# RpiServoStepper_v3.net
KiCad netlist of a schematic drawn in EAGLE
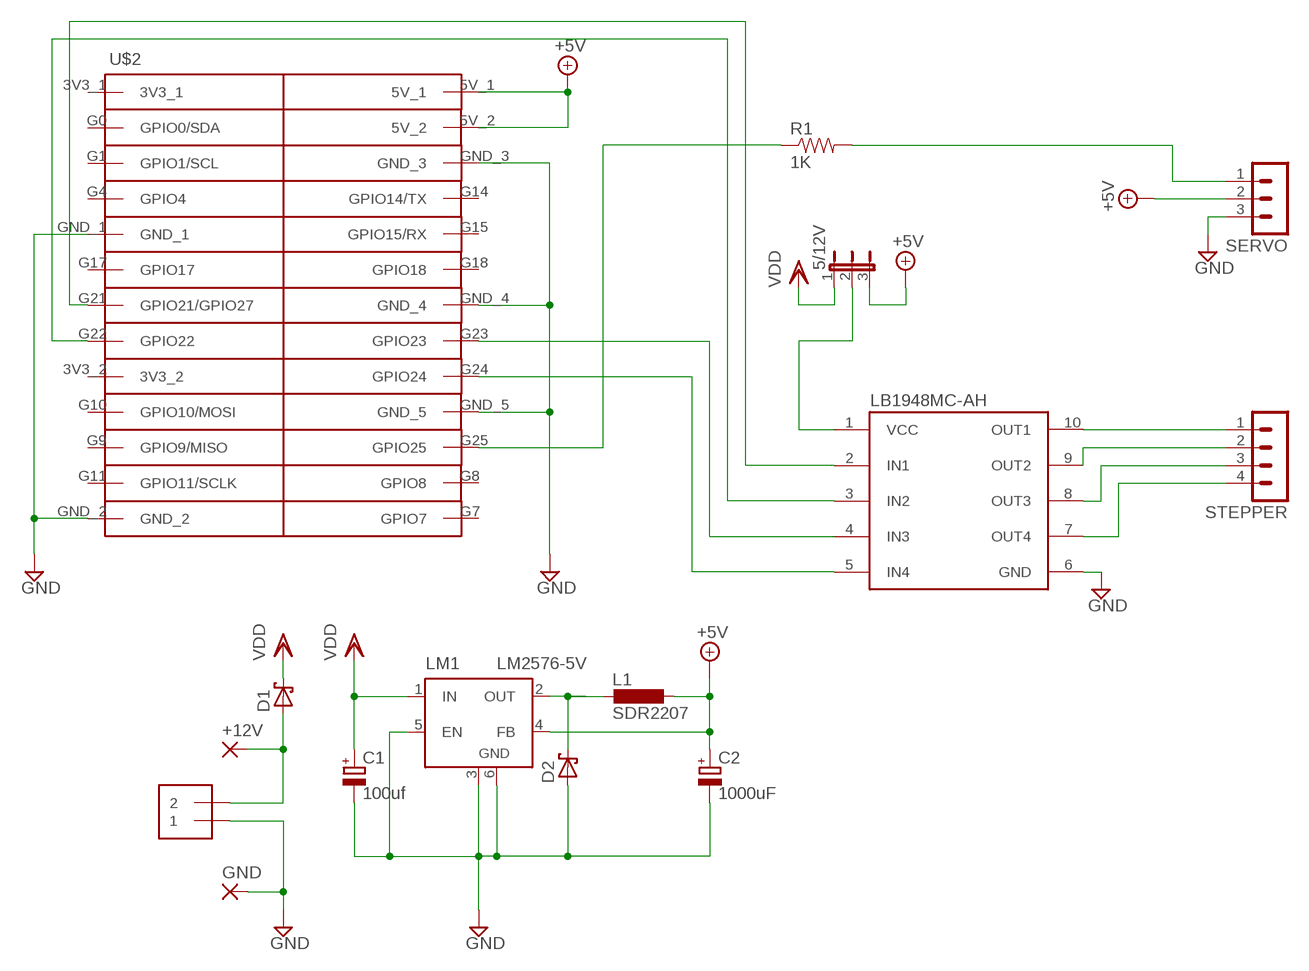
[diagram p0: schematic, sheet 1]

(export (version "E")
  (design (tool "Eeschema 10.0.6"))
  (components
    (comp (ref "+12V")
      (value "3,81/1,4")
      (footprint "eagle-import:3,81_1,4")
      (libsource (lib "eagle-import") (part "3,81/1,4"))
    )
    (comp (ref "5/12V")
      (value "JP2E")
      (footprint "eagle-import:JP2")
      (libsource (lib "eagle-import") (part "JP2E"))
    )
    (comp (ref "C1")
      (value "100uf")
      (footprint "eagle-import:PANASONIC_E")
      (libsource (lib "eagle-import") (part "CPOL-EUE"))
    )
    (comp (ref "C2")
      (value "1000uF")
      (footprint "eagle-import:PANASONIC_G")
      (libsource (lib "eagle-import") (part "CPOL-EUG"))
    )
    (comp (ref "D1")
      (value "SCHOTTKY-DIODESMC")
      (footprint "eagle-import:SMC")
      (libsource (lib "eagle-import") (part "SCHOTTKY-DIODESMC"))
    )
    (comp (ref "D2")
      (value "SCHOTTKY-DIODESMC")
      (footprint "eagle-import:SMC")
      (libsource (lib "eagle-import") (part "SCHOTTKY-DIODESMC"))
    )
    (comp (ref "GND")
      (value "3,81/1,4")
      (footprint "eagle-import:3,81_1,4")
      (libsource (lib "eagle-import") (part "3,81/1,4"))
    )
    (comp (ref "J1")
      (value "1X2-3.5MM")
      (footprint "eagle-import:3.5MMTERM")
      (libsource (lib "eagle-import") (part "1X2-3.5MM"))
    )
    (comp (ref "L1")
      (value "SDR2207")
      (footprint "eagle-import:SM")
      (libsource (lib "eagle-import") (part "SDR2207"))
    )
    (comp (ref "LB1948MC-AH")
      (value "LB1948MC-AH")
      (footprint "eagle-import:SOIC-10")
      (libsource (lib "eagle-import") (part "LB1948MC-AH"))
    )
    (comp (ref "LM1")
      (value "LM2576-5V")
      (footprint "eagle-import:TO263-5")
      (libsource (lib "eagle-import") (part "LM2596S"))
    )
    (comp (ref "R1")
      (value "1K")
      (footprint "eagle-import:1206")
      (libsource (lib "eagle-import") (part "RESISTOR1206"))
    )
    (comp (ref "SERVO")
      (value "MA03-1")
      (footprint "eagle-import:MA03-1")
      (libsource (lib "eagle-import") (part "MA03-1"))
    )
    (comp (ref "STEPPER")
      (value "MA04-1")
      (footprint "eagle-import:MA04-1")
      (libsource (lib "eagle-import") (part "MA04-1"))
    )
    (comp (ref "U$2")
      (value "CONNECTEUR_RPI")
      (footprint "eagle-import:26PIN")
      (libsource (lib "eagle-import") (part "CONNECTEUR_RPI"))
    )
  )
  (nets
    (net (code "1") (name "+5V") (class "Default")
      (node (ref "5/12V") (pin "3") (pinfunction "3_3") (pintype "passive"))
      (node (ref "C2") (pin "+") (pinfunction "+_+") (pintype "passive"))
      (node (ref "L1") (pin "P$2") (pinfunction "2_P$2") (pintype "passive"))
      (node (ref "LM1") (pin "4") (pinfunction "FB_4") (pintype "input"))
      (node (ref "SERVO") (pin "2") (pinfunction "2_2") (pintype "passive"))
      (node (ref "U$2") (pin "5V_1") (pinfunction "5V_1_5V_1") (pintype "bidirectional"))
      (node (ref "U$2") (pin "5V_2") (pinfunction "5V_2_5V_2") (pintype "bidirectional"))
    )
    (net (code "2") (name "GND") (class "Default")
      (node (ref "C1") (pin "-") (pinfunction "-_-") (pintype "passive"))
      (node (ref "C2") (pin "-") (pinfunction "-_-") (pintype "passive"))
      (node (ref "D2") (pin "A") (pinfunction "A_A") (pintype "passive"))
      (node (ref "GND") (pin "1") (pinfunction "P_1") (pintype "passive"))
      (node (ref "J1") (pin "1") (pinfunction "1_1") (pintype "passive"))
      (node (ref "LB1948MC-AH") (pin "6") (pinfunction "GND_6") (pintype "bidirectional"))
      (node (ref "LM1") (pin "3") (pinfunction "GND_3") (pintype "power_in"))
      (node (ref "LM1") (pin "5") (pinfunction "EN_5") (pintype "input"))
      (node (ref "LM1") (pin "6") (pinfunction "GND_6") (pintype "power_in"))
      (node (ref "SERVO") (pin "3") (pinfunction "3_3") (pintype "passive"))
      (node (ref "U$2") (pin "GND_1") (pinfunction "GND_1_GND_1") (pintype "bidirectional"))
      (node (ref "U$2") (pin "GND_2") (pinfunction "GND_2_GND_2") (pintype "bidirectional"))
      (node (ref "U$2") (pin "GND_3") (pinfunction "GND_3_GND_3") (pintype "bidirectional"))
      (node (ref "U$2") (pin "GND_4") (pinfunction "GND_4_GND_4") (pintype "bidirectional"))
      (node (ref "U$2") (pin "GND_5") (pinfunction "GND_5_GND_5") (pintype "bidirectional"))
    )
    (net (code "3") (name "Net-(+12V-P)") (class "Default")
      (node (ref "+12V") (pin "1") (pinfunction "P_1") (pintype "passive"))
      (node (ref "D1") (pin "A") (pinfunction "A_A") (pintype "passive"))
      (node (ref "J1") (pin "2") (pinfunction "2_2") (pintype "passive"))
    )
    (net (code "4") (name "Net-(L1-1)") (class "Default")
      (node (ref "D2") (pin "C") (pinfunction "C_C") (pintype "passive"))
      (node (ref "L1") (pin "P$1") (pinfunction "1_P$1") (pintype "passive"))
      (node (ref "LM1") (pin "2") (pinfunction "OUT_2") (pintype "output"))
    )
    (net (code "5") (name "Net-(LB1948MC-AH-IN1)") (class "Default")
      (node (ref "LB1948MC-AH") (pin "2") (pinfunction "IN1_2") (pintype "bidirectional"))
      (node (ref "U$2") (pin "G21") (pinfunction "GPIO21/GPIO27_G21") (pintype "bidirectional"))
    )
    (net (code "6") (name "Net-(LB1948MC-AH-IN2)") (class "Default")
      (node (ref "LB1948MC-AH") (pin "3") (pinfunction "IN2_3") (pintype "bidirectional"))
      (node (ref "U$2") (pin "G22") (pinfunction "GPIO22_G22") (pintype "bidirectional"))
    )
    (net (code "7") (name "Net-(LB1948MC-AH-IN3)") (class "Default")
      (node (ref "LB1948MC-AH") (pin "4") (pinfunction "IN3_4") (pintype "bidirectional"))
      (node (ref "U$2") (pin "G23") (pinfunction "GPIO23_G23") (pintype "bidirectional"))
    )
    (net (code "8") (name "Net-(LB1948MC-AH-IN4)") (class "Default")
      (node (ref "LB1948MC-AH") (pin "5") (pinfunction "IN4_5") (pintype "bidirectional"))
      (node (ref "U$2") (pin "G24") (pinfunction "GPIO24_G24") (pintype "bidirectional"))
    )
    (net (code "9") (name "Net-(LB1948MC-AH-OUT1)") (class "Default")
      (node (ref "LB1948MC-AH") (pin "10") (pinfunction "OUT1_10") (pintype "bidirectional"))
      (node (ref "STEPPER") (pin "1") (pinfunction "1_1") (pintype "passive"))
    )
    (net (code "10") (name "Net-(LB1948MC-AH-OUT2)") (class "Default")
      (node (ref "LB1948MC-AH") (pin "9") (pinfunction "OUT2_9") (pintype "bidirectional"))
      (node (ref "STEPPER") (pin "2") (pinfunction "2_2") (pintype "passive"))
    )
    (net (code "11") (name "Net-(LB1948MC-AH-OUT3)") (class "Default")
      (node (ref "LB1948MC-AH") (pin "8") (pinfunction "OUT3_8") (pintype "bidirectional"))
      (node (ref "STEPPER") (pin "3") (pinfunction "3_3") (pintype "passive"))
    )
    (net (code "12") (name "Net-(LB1948MC-AH-OUT4)") (class "Default")
      (node (ref "LB1948MC-AH") (pin "7") (pinfunction "OUT4_7") (pintype "bidirectional"))
      (node (ref "STEPPER") (pin "4") (pinfunction "4_4") (pintype "passive"))
    )
    (net (code "13") (name "Net-(LB1948MC-AH-VCC)") (class "Default")
      (node (ref "5/12V") (pin "2") (pinfunction "2_2") (pintype "passive"))
      (node (ref "LB1948MC-AH") (pin "1") (pinfunction "VCC_1") (pintype "bidirectional"))
    )
    (net (code "14") (name "Net-(R1-Pad2)") (class "Default")
      (node (ref "R1") (pin "2") (pinfunction "2_2") (pintype "passive"))
      (node (ref "SERVO") (pin "1") (pinfunction "1_1") (pintype "passive"))
    )
    (net (code "15") (name "Net-(U$2-GPIO25)") (class "Default")
      (node (ref "R1") (pin "1") (pinfunction "1_1") (pintype "passive"))
      (node (ref "U$2") (pin "G25") (pinfunction "GPIO25_G25") (pintype "bidirectional"))
    )
    (net (code "16") (name "VDD") (class "Default")
      (node (ref "5/12V") (pin "1") (pinfunction "1_1") (pintype "passive"))
      (node (ref "C1") (pin "+") (pinfunction "+_+") (pintype "passive"))
      (node (ref "D1") (pin "C") (pinfunction "C_C") (pintype "passive"))
      (node (ref "LM1") (pin "1") (pinfunction "IN_1") (pintype "input"))
    )
    (net (code "17") (name "unconnected-(U$2-GPIO0{slash}SDA-PadG0)") (class "Default")
      (node (ref "U$2") (pin "G0") (pinfunction "GPIO0/SDA_G0") (pintype "bidirectional"))
    )
    (net (code "18") (name "unconnected-(U$2-GPIO1{slash}SCL-PadG1)") (class "Default")
      (node (ref "U$2") (pin "G1") (pinfunction "GPIO1/SCL_G1") (pintype "bidirectional"))
    )
    (net (code "19") (name "unconnected-(U$2-GPIO4-PadG4)") (class "Default")
      (node (ref "U$2") (pin "G4") (pinfunction "GPIO4_G4") (pintype "bidirectional"))
    )
    (net (code "20") (name "unconnected-(U$2-GPIO7-PadG7)") (class "Default")
      (node (ref "U$2") (pin "G7") (pinfunction "GPIO7_G7") (pintype "bidirectional"))
    )
    (net (code "21") (name "unconnected-(U$2-GPIO8-PadG8)") (class "Default")
      (node (ref "U$2") (pin "G8") (pinfunction "GPIO8_G8") (pintype "bidirectional"))
    )
    (net (code "22") (name "unconnected-(U$2-GPIO9{slash}MISO-PadG9)") (class "Default")
      (node (ref "U$2") (pin "G9") (pinfunction "GPIO9/MISO_G9") (pintype "bidirectional"))
    )
    (net (code "23") (name "unconnected-(U$2-GPIO10{slash}MOSI-PadG10)") (class "Default")
      (node (ref "U$2") (pin "G10") (pinfunction "GPIO10/MOSI_G10") (pintype "bidirectional"))
    )
    (net (code "24") (name "unconnected-(U$2-GPIO11{slash}SCLK-PadG11)") (class "Default")
      (node (ref "U$2") (pin "G11") (pinfunction "GPIO11/SCLK_G11") (pintype "bidirectional"))
    )
    (net (code "25") (name "unconnected-(U$2-GPIO14{slash}TX-PadG14)") (class "Default")
      (node (ref "U$2") (pin "G14") (pinfunction "GPIO14/TX_G14") (pintype "bidirectional"))
    )
    (net (code "26") (name "unconnected-(U$2-GPIO15{slash}RX-PadG15)") (class "Default")
      (node (ref "U$2") (pin "G15") (pinfunction "GPIO15/RX_G15") (pintype "bidirectional"))
    )
    (net (code "27") (name "unconnected-(U$2-GPIO17-PadG17)") (class "Default")
      (node (ref "U$2") (pin "G17") (pinfunction "GPIO17_G17") (pintype "bidirectional"))
    )
    (net (code "28") (name "unconnected-(U$2-GPIO18-PadG18)") (class "Default")
      (node (ref "U$2") (pin "G18") (pinfunction "GPIO18_G18") (pintype "bidirectional"))
    )
    (net (code "29") (name "unconnected-(U$2-Pad3V3_1)") (class "Default")
      (node (ref "U$2") (pin "3V3_1") (pinfunction "3V3_1_3V3_1") (pintype "bidirectional"))
    )
    (net (code "30") (name "unconnected-(U$2-Pad3V3_2)") (class "Default")
      (node (ref "U$2") (pin "3V3_2") (pinfunction "3V3_2_3V3_2") (pintype "bidirectional"))
    )
  )
)
